# det.net
KiCad netlist of a schematic drawn in Altium Designer
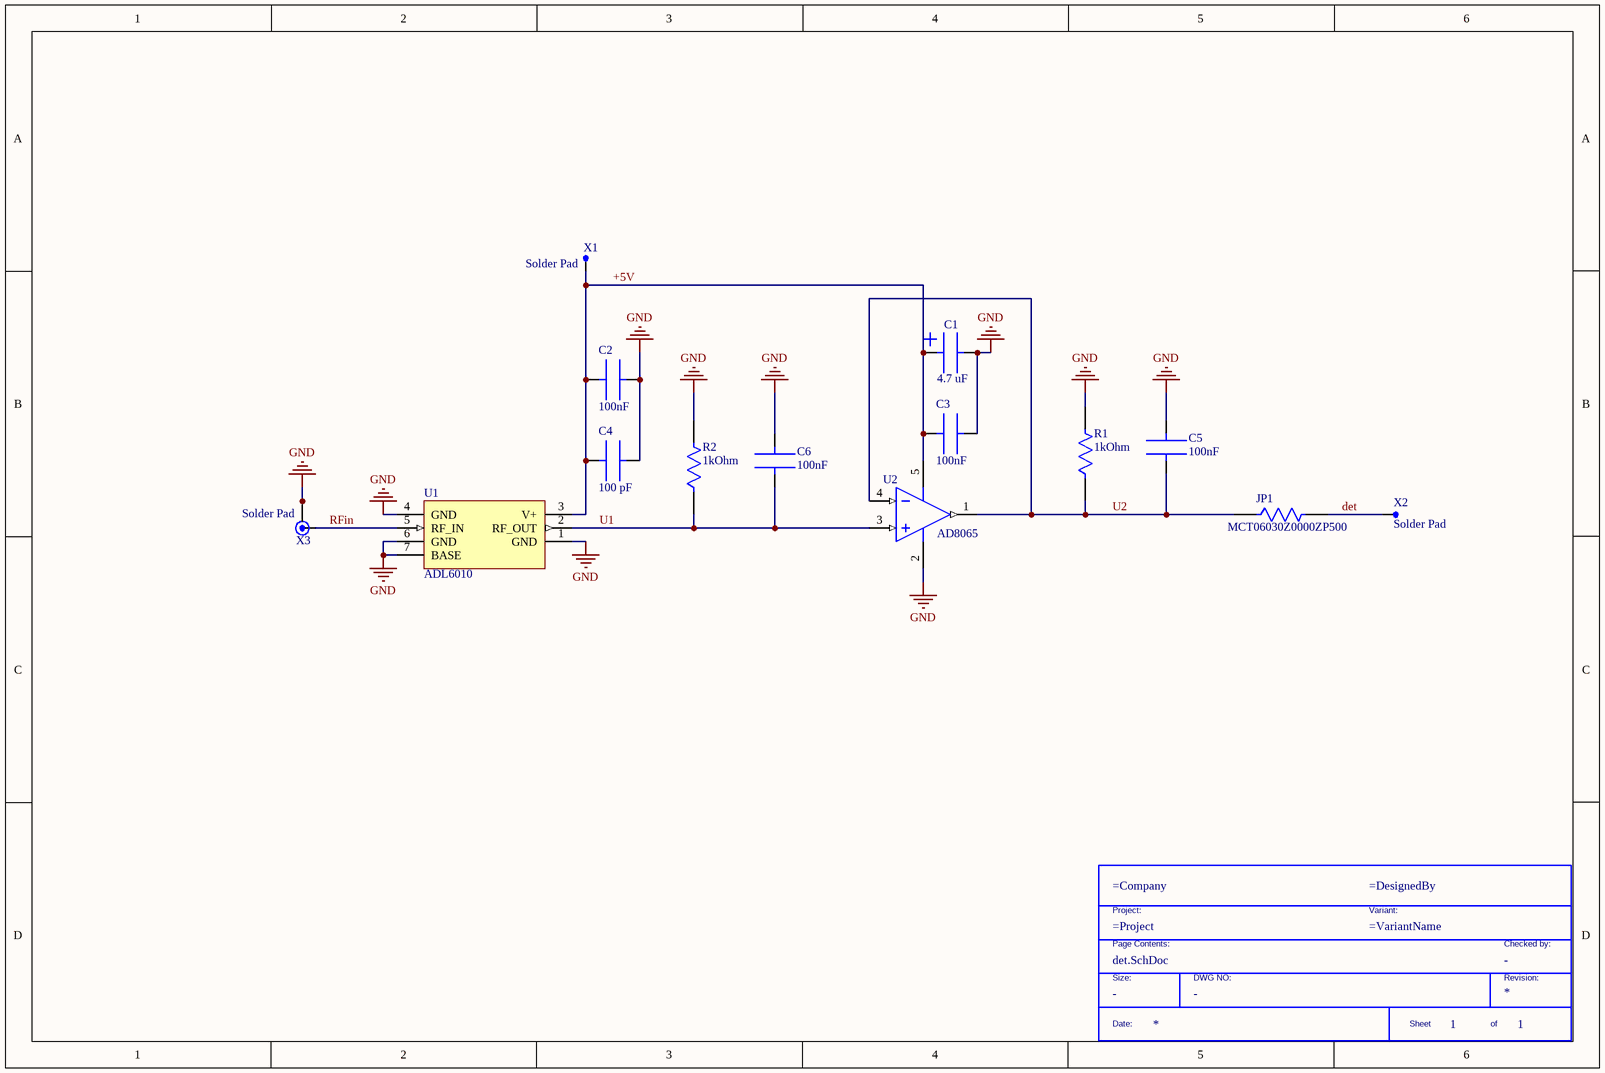
[diagram p0: det.SchDoc]

(export (version "E")
  (design (tool "Eeschema 10.0.6"))
  (components
    (comp (ref "*")
      (value "TitleBlock")
      (description "Standard Title Block")
      (fields (field (name "DWG NO") "-") (field (name "SIZE") "-") (field (name "CHECKED BY") "-"))
      (libsource (lib "amp") (part "TitleBlock"))
    )
    (comp (ref "C1")
      (value "4.7 uF")
      (footprint "C4_7uF")
      (fields
        (field (name "MANUFACTURER") "Vishay Sprague")
        (field (name "MANUFACTURER PART NUMBER") "TH3A475K010C2900")
      )
      (libsource (lib "det") (part "C7_4uF_TH3A475K010C2900"))
    )
    (comp (ref "C2")
      (value "100nF")
      (footprint "C1000pF__C100nF")
      (fields
        (field (name "MANUFACTURER") "Murata")
        (field (name "MANUFACTURER PART NUMBER") "GCM188R71C104KA37J")
      )
      (libsource (lib "det") (part "C100nF_GCM188R71C104KA37J"))
    )
    (comp (ref "C3")
      (value "100nF")
      (footprint "C1000pF__C100nF")
      (fields
        (field (name "MANUFACTURER") "Murata")
        (field (name "MANUFACTURER PART NUMBER") "GCM188R71C104KA37J")
      )
      (libsource (lib "det") (part "C100nF_GCM188R71C104KA37J"))
    )
    (comp (ref "C4")
      (value "100 pF")
      (footprint "C100pF")
      (description "Multilayer Ceramic Capacitors MLCC - SMD/SMT 100 pF 100 VDC 1% 0402 C0G (NP0)")
      (fields
        (field (name "MANUFACTURER") "Murata")
        (field (name "MANUFACTURER PART NUMBER") "GRM1555C2A101FA01D")
      )
      (libsource (lib "det") (part "C100pF_GRM1555C2A101FA01D"))
    )
    (comp (ref "C5")
      (value "100nF")
      (footprint "C1000pF__C100nF")
      (fields
        (field (name "MANUFACTURER") "Murata")
        (field (name "MANUFACTURER PART NUMBER") "GCM188R71C104KA37J")
      )
      (libsource (lib "det") (part "C100nF_GCM188R71C104KA37J"))
    )
    (comp (ref "C6")
      (value "100nF")
      (footprint "C1000pF__C100nF")
      (fields
        (field (name "MANUFACTURER") "Murata")
        (field (name "MANUFACTURER PART NUMBER") "GCM188R71C104KA37J")
      )
      (libsource (lib "det") (part "C100nF_GCM188R71C104KA37J"))
    )
    (comp (ref "JP1")
      (value "MCT06030Z0000ZP500")
      (footprint "JP_R_MCT06030Z0000ZP500")
      (description "Fixed Resistor, Thin Film, 0.1W, 0ohm, Surface Mount, 0603")
      (fields (field (name "MANUFACTURER") "Vishay Beyschlag") (field (name "POWER") "100mW"))
      (libsource (lib "det") (part "JP_small_MCT06030Z0000ZP500"))
    )
    (comp (ref "R1")
      (value "1kOhm")
      (footprint "JP_R_MCT06030Z0000ZP500")
      (description "Fixed Resistor, Thin Film, 0.1W, 1000ohm, 75V, 1% +/-Tol, 50ppm/Cel, Surface Mount, 0603")
      (fields
        (field (name "MANUFACTURER") "Vishay BCcomponents")
        (field (name "MANUFACTURER PART NUMBER") "MCT06030C1001FPW00")
      )
      (libsource (lib "det") (part "R_1kOhm_MCT06030C1001FPW00"))
    )
    (comp (ref "R2")
      (value "1kOhm")
      (footprint "JP_R_MCT06030Z0000ZP500")
      (description "Fixed Resistor, Thin Film, 0.1W, 1000ohm, 75V, 1% +/-Tol, 50ppm/Cel, Surface Mount, 0603")
      (fields
        (field (name "MANUFACTURER") "Vishay BCcomponents")
        (field (name "MANUFACTURER PART NUMBER") "MCT06030C1001FPW00")
      )
      (libsource (lib "det") (part "R_1kOhm_MCT06030C1001FPW00"))
    )
    (comp (ref "U1")
      (value "ADL6010")
      (footprint "Det_ADL6010ACPZN-R2")
      (description "Linear Detector, 500MHz Min, 43500MHz Max, 20dBm Input Power-Max")
      (fields
        (field (name "MANUFACTURER") "Analog Devices")
        (field (name "MANUFACTURER PART NUMBER") "ADL6010ACPZN-R2")
      )
      (libsource (lib "det") (part "det_ADL6010ACPZN-R2"))
    )
    (comp (ref "U2")
      (value "AD8065")
      (footprint "opAmp_AD8065ARTZ-REEL7")
      (description "Operational Amplifier, 1 Func, BIPolar, PDSO5")
      (fields
        (field (name "MANUFACTURER") "Analog Devices")
        (field (name "MANUFACTURER PART NUMBER") "AD8065ARTZ-REEL7")
      )
      (libsource (lib "det") (part "opAmp_AD8065ARTZ-REEL7"))
    )
    (comp (ref "X1")
      (value "Solder Pad")
      (footprint "Solder Pad")
      (description "Pad to solder wires to")
      (libsource (lib "det") (part "Solder Pad"))
    )
    (comp (ref "X2")
      (value "Solder Pad")
      (footprint "Solder Pad")
      (description "Pad to solder wires to")
      (libsource (lib "det") (part "Solder Pad"))
    )
    (comp (ref "X3")
      (value "Solder Pad")
      (footprint "CPW Edge Connector")
      (description "Solder pad for RF Coplanar Waveguide Rogers 4350B Thickness 0.020\" Copper 1oz")
      (libsource (lib "det") (part "RF  CPW Solder Pad"))
    )
  )
  (nets
    (net (code "1") (name "/+5V") (class "Default")
      (node (ref "C1") (pin "1") (pinfunction "+_1") (pintype "passive"))
      (node (ref "C2") (pin "1") (pinfunction "1_1") (pintype "passive"))
      (node (ref "C3") (pin "1") (pinfunction "1_1") (pintype "passive"))
      (node (ref "C4") (pin "1") (pinfunction "1_1") (pintype "passive"))
      (node (ref "U1") (pin "3") (pinfunction "V+_3") (pintype "passive"))
      (node (ref "U2") (pin "5") (pinfunction "+VS_5") (pintype "power_in"))
      (node (ref "X1") (pin "1") (pinfunction "1_1") (pintype "passive"))
    )
    (net (code "2") (name "/RFin") (class "Default")
      (node (ref "U1") (pin "5") (pinfunction "RF_IN_5") (pintype "input"))
      (node (ref "X3") (pin "1") (pinfunction "1_1") (pintype "passive"))
    )
    (net (code "3") (name "/U1") (class "Default")
      (node (ref "C6") (pin "1") (pinfunction "1_1") (pintype "passive"))
      (node (ref "R2") (pin "1") (pinfunction "1_1") (pintype "passive"))
      (node (ref "U1") (pin "2") (pinfunction "RF_OUT_2") (pintype "output"))
      (node (ref "U2") (pin "3") (pinfunction "+IN_3") (pintype "input"))
    )
    (net (code "4") (name "/U2") (class "Default")
      (node (ref "C5") (pin "1") (pinfunction "1_1") (pintype "passive"))
      (node (ref "JP1") (pin "1") (pinfunction "1_1") (pintype "passive"))
      (node (ref "R1") (pin "1") (pinfunction "1_1") (pintype "passive"))
      (node (ref "U2") (pin "1") (pinfunction "VOUT_1") (pintype "output"))
      (node (ref "U2") (pin "4") (pinfunction "-IN_4") (pintype "input"))
    )
    (net (code "5") (name "/det") (class "Default")
      (node (ref "JP1") (pin "2") (pinfunction "2_2") (pintype "passive"))
      (node (ref "X2") (pin "1") (pinfunction "1_1") (pintype "passive"))
    )
    (net (code "6") (name "GND") (class "Default")
      (node (ref "C1") (pin "2") (pinfunction "2_2") (pintype "passive"))
      (node (ref "C2") (pin "2") (pinfunction "2_2") (pintype "passive"))
      (node (ref "C3") (pin "2") (pinfunction "2_2") (pintype "passive"))
      (node (ref "C4") (pin "2") (pinfunction "2_2") (pintype "passive"))
      (node (ref "C5") (pin "2") (pinfunction "2_2") (pintype "passive"))
      (node (ref "C6") (pin "2") (pinfunction "2_2") (pintype "passive"))
      (node (ref "R1") (pin "2") (pinfunction "2_2") (pintype "passive"))
      (node (ref "R2") (pin "2") (pinfunction "2_2") (pintype "passive"))
      (node (ref "U1") (pin "1") (pinfunction "GND_1") (pintype "passive"))
      (node (ref "U1") (pin "4") (pinfunction "GND_4") (pintype "passive"))
      (node (ref "U1") (pin "6") (pinfunction "GND_6") (pintype "passive"))
      (node (ref "U1") (pin "7") (pinfunction "BASE_7") (pintype "passive"))
      (node (ref "U2") (pin "2") (pinfunction "-VS_2") (pintype "power_in"))
      (node (ref "X3") (pin "2") (pinfunction "2_2") (pintype "passive"))
      (node (ref "X3") (pin "3") (pinfunction "3_3") (pintype "passive"))
    )
  )
)
